# FC_Sheet2.net
KiCad netlist of a schematic drawn in Altium Designer
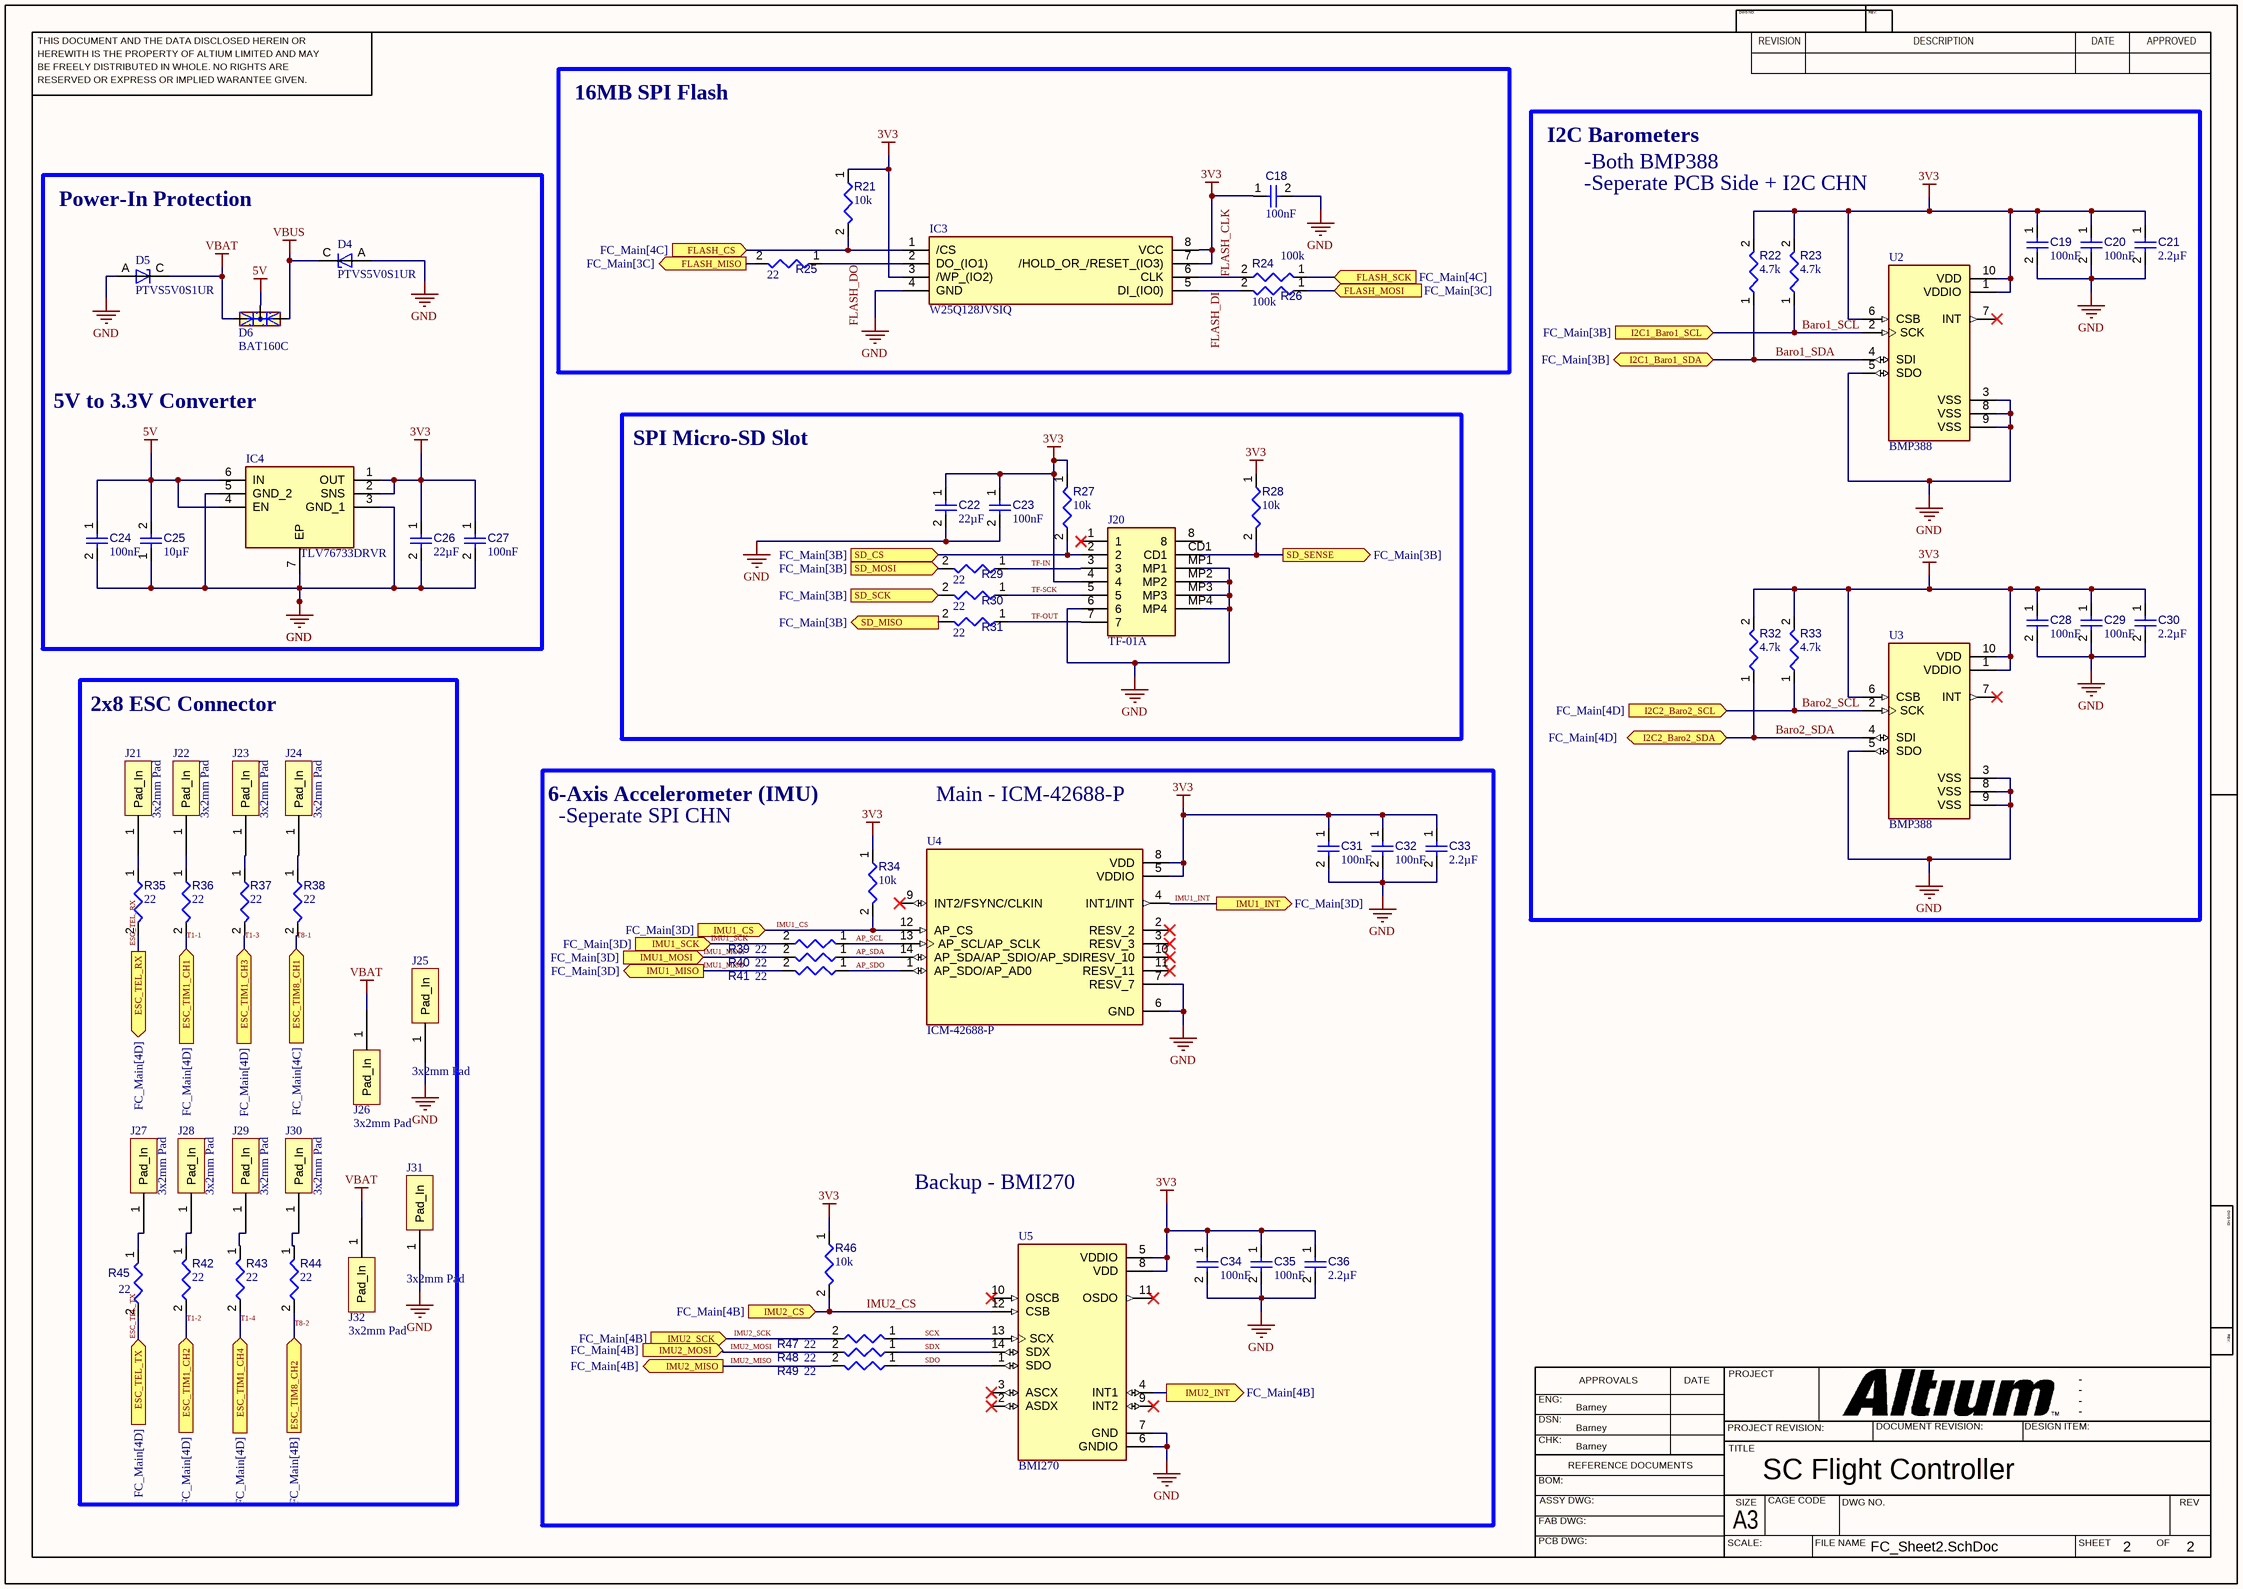
[diagram p0: FC_Sheet2.SchDoc]

(export (version "E")
  (design (tool "Eeschema 10.0.6"))
  (components
    (comp (ref "C18")
      (value "100nF")
      (footprint "CAPC0402(1005)60_L")
      (description "Chip Capacitor, 100nF +/-20%, 10V, 0402, Thickness 0.6 mm")
      (fields (field (name "TOLERANCE") "20%") (field (name "Comment") "Capacitor 100nF +/-20% 10V 0402"))
      (libsource (lib "Barney's Workspace") (part "CAP-NP-2"))
    )
    (comp (ref "C19")
      (value "100nF")
      (footprint "CAPC0402(1005)60_L")
      (description "Chip Capacitor, 100nF +/-20%, 10V, 0402, Thickness 0.6 mm")
      (fields (field (name "TOLERANCE") "20%") (field (name "Comment") "Capacitor 100nF +/-20% 10V 0402"))
      (libsource (lib "Barney's Workspace") (part "CAP-NP-2"))
    )
    (comp (ref "C20")
      (value "100nF")
      (footprint "CAPC0402(1005)60_L")
      (description "Chip Capacitor, 100nF +/-20%, 10V, 0402, Thickness 0.6 mm")
      (fields (field (name "TOLERANCE") "20%") (field (name "Comment") "Capacitor 100nF +/-20% 10V 0402"))
      (libsource (lib "Barney's Workspace") (part "CAP-NP-2"))
    )
    (comp (ref "C21")
      (value "2.2µF")
      (footprint "CAPC0402(1005)60_L")
      (description "Chip Capacitor, 2,2µF +/-20%, 10V, 0402, Thickness 0.6 mm")
      (fields (field (name "TOLERANCE") "10%") (field (name "Comment") "Capacitor 2,2µF +/-20% 10V 0402"))
      (libsource (lib "Barney's Workspace") (part "CAP-NP-2"))
    )
    (comp (ref "C22")
      (value "22µF")
      (footprint "CAPC0805(2012)145_L")
      (description "Chip Capacitor, 22µF +/-40%, 16V, 0805, Thickness 1.45 mm")
      (fields (field (name "TOLERANCE") "5%") (field (name "Comment") "Capacitor 22µF +/-40% 16V 0805"))
      (libsource (lib "Barney's Workspace") (part "CAP-NP-2"))
    )
    (comp (ref "C23")
      (value "100nF")
      (footprint "CAPC0402(1005)60_L")
      (description "Chip Capacitor, 100nF +/-20%, 10V, 0402, Thickness 0.6 mm")
      (fields (field (name "TOLERANCE") "20%") (field (name "Comment") "Capacitor 100nF +/-20% 10V 0402"))
      (libsource (lib "Barney's Workspace") (part "CAP-NP-2"))
    )
    (comp (ref "C24")
      (value "100nF")
      (footprint "CAPC0402(1005)60_L")
      (description "Chip Capacitor, 100nF +/-20%, 10V, 0402, Thickness 0.6 mm")
      (fields (field (name "TOLERANCE") "20%") (field (name "Comment") "Capacitor 100nF +/-20% 10V 0402"))
      (libsource (lib "Barney's Workspace") (part "CAP-NP-2"))
    )
    (comp (ref "C25")
      (value "10µF")
      (footprint "CAPC0603(1608)100_L")
      (description "Chip Capacitor, 10µF +/-20%, 10V, 0603, Thickness 1 mm")
      (fields (field (name "TOLERANCE") "10%") (field (name "Comment") "Capacitor 10µF +/-20% 10V 0603"))
      (libsource (lib "Barney's Workspace") (part "CAP-NP-2"))
    )
    (comp (ref "C26")
      (value "22µF")
      (footprint "CAPC0805(2012)145_L")
      (description "Chip Capacitor, 22µF +/-40%, 16V, 0805, Thickness 1.45 mm")
      (fields (field (name "TOLERANCE") "5%") (field (name "Comment") "Capacitor 22µF +/-40% 16V 0805"))
      (libsource (lib "Barney's Workspace") (part "CAP-NP-2"))
    )
    (comp (ref "C27")
      (value "100nF")
      (footprint "CAPC0402(1005)60_L")
      (description "Chip Capacitor, 100nF +/-20%, 10V, 0402, Thickness 0.6 mm")
      (fields (field (name "TOLERANCE") "20%") (field (name "Comment") "Capacitor 100nF +/-20% 10V 0402"))
      (libsource (lib "Barney's Workspace") (part "CAP-NP-2"))
    )
    (comp (ref "C28")
      (value "100nF")
      (footprint "CAPC0402(1005)60_L")
      (description "Chip Capacitor, 100nF +/-20%, 10V, 0402, Thickness 0.6 mm")
      (fields (field (name "TOLERANCE") "20%") (field (name "Comment") "Capacitor 100nF +/-20% 10V 0402"))
      (libsource (lib "Barney's Workspace") (part "CAP-NP-2"))
    )
    (comp (ref "C29")
      (value "100nF")
      (footprint "CAPC0402(1005)60_L")
      (description "Chip Capacitor, 100nF +/-20%, 10V, 0402, Thickness 0.6 mm")
      (fields (field (name "TOLERANCE") "20%") (field (name "Comment") "Capacitor 100nF +/-20% 10V 0402"))
      (libsource (lib "Barney's Workspace") (part "CAP-NP-2"))
    )
    (comp (ref "C30")
      (value "2.2µF")
      (footprint "CAPC0402(1005)60_L")
      (description "Chip Capacitor, 2,2µF +/-20%, 10V, 0402, Thickness 0.6 mm")
      (fields (field (name "TOLERANCE") "10%") (field (name "Comment") "Capacitor 2,2µF +/-20% 10V 0402"))
      (libsource (lib "Barney's Workspace") (part "CAP-NP-2"))
    )
    (comp (ref "C31")
      (value "100nF")
      (footprint "CAPC0402(1005)60_L")
      (description "Chip Capacitor, 100nF +/-20%, 10V, 0402, Thickness 0.6 mm")
      (fields (field (name "TOLERANCE") "20%") (field (name "Comment") "Capacitor 100nF +/-20% 10V 0402"))
      (libsource (lib "Barney's Workspace") (part "CAP-NP-2"))
    )
    (comp (ref "C32")
      (value "100nF")
      (footprint "CAPC0402(1005)60_L")
      (description "Chip Capacitor, 100nF +/-20%, 10V, 0402, Thickness 0.6 mm")
      (fields (field (name "TOLERANCE") "20%") (field (name "Comment") "Capacitor 100nF +/-20% 10V 0402"))
      (libsource (lib "Barney's Workspace") (part "CAP-NP-2"))
    )
    (comp (ref "C33")
      (value "2.2µF")
      (footprint "CAPC0402(1005)60_L")
      (description "Chip Capacitor, 2,2µF +/-20%, 10V, 0402, Thickness 0.6 mm")
      (fields (field (name "TOLERANCE") "10%") (field (name "Comment") "Capacitor 2,2µF +/-20% 10V 0402"))
      (libsource (lib "Barney's Workspace") (part "CAP-NP-2"))
    )
    (comp (ref "C34")
      (value "100nF")
      (footprint "CAPC0402(1005)60_L")
      (description "Chip Capacitor, 100nF +/-20%, 10V, 0402, Thickness 0.6 mm")
      (fields (field (name "TOLERANCE") "20%") (field (name "Comment") "Capacitor 100nF +/-20% 10V 0402"))
      (libsource (lib "Barney's Workspace") (part "CAP-NP-2"))
    )
    (comp (ref "C35")
      (value "100nF")
      (footprint "CAPC0402(1005)60_L")
      (description "Chip Capacitor, 100nF +/-20%, 10V, 0402, Thickness 0.6 mm")
      (fields (field (name "TOLERANCE") "20%") (field (name "Comment") "Capacitor 100nF +/-20% 10V 0402"))
      (libsource (lib "Barney's Workspace") (part "CAP-NP-2"))
    )
    (comp (ref "C36")
      (value "2.2µF")
      (footprint "CAPC0402(1005)60_L")
      (description "Chip Capacitor, 2,2µF +/-20%, 10V, 0402, Thickness 0.6 mm")
      (fields (field (name "TOLERANCE") "10%") (field (name "Comment") "Capacitor 2,2µF +/-20% 10V 0402"))
      (libsource (lib "Barney's Workspace") (part "CAP-NP-2"))
    )
    (comp (ref "D4")
      (value "PTVS5V0S1UR")
      (footprint "TVS_PTVS5V0S1UR")
      (description "9.2V Clamp 43.5A Ipp Tvs Diode Surface Mount SOD-123W")
      (fields (field (name "MF") "Nexperia USA"))
      (libsource (lib "Barney's Workspace") (part "PTVS5V0S1UR"))
    )
    (comp (ref "D5")
      (value "PTVS5V0S1UR")
      (footprint "TVS_PTVS5V0S1UR")
      (description "9.2V Clamp 43.5A Ipp Tvs Diode Surface Mount SOD-123W")
      (fields (field (name "MF") "Nexperia USA"))
      (libsource (lib "Barney's Workspace") (part "PTVS5V0S1UR"))
    )
    (comp (ref "D6")
      (value "BAT160C")
      (footprint "SOT223")
      (description "Diode Array 1 Pair Common Cathode Schottky 60 V 1A (DC) Surface Mount TO-261-4, TO-261AA")
      (fields (field (name "MF") "NXP Semiconductors"))
      (libsource (lib "Barney's Workspace") (part "BAT160C"))
    )
    (comp (ref "IC3")
      (value "W25Q128JVSIQ")
      (footprint "SamacSys:SOIC127P790X216-8N")
      (description "Integrated Circuit")
      (fields (field (name "MOUSER PART NUMBER") "454-W25Q128JVSIQ"))
      (libsource (lib "*") (part "W25Q128JVSIQ"))
    )
    (comp (ref "IC4")
      (value "TLV76733DRVR")
      (footprint "SamacSys:SON65P200X200X80-7N")
      (description "Integrated Circuit")
      (fields (field (name "MOUSER PART NUMBER") "595-TLV76733DRVR"))
      (libsource (lib "*") (part "TLV76733DRVR"))
    )
    (comp (ref "J20")
      (value "TF-01A")
      (footprint "SamacSys:TF01A")
      (description "Connector")
      (libsource (lib "*") (part "TF-01A"))
    )
    (comp (ref "J21")
      (value "3x2mm Pad")
      (footprint "3x2mm Pad-Footprint-1")
      (description "3mm x 2mm Pad to solder")
      (libsource (lib "") (part "3x2mm Pad-Symbol-1_1"))
    )
    (comp (ref "J22")
      (value "3x2mm Pad")
      (footprint "3x2mm Pad-Footprint-1")
      (description "3mm x 2mm Pad to solder")
      (libsource (lib "") (part "3x2mm Pad-Symbol-1_1"))
    )
    (comp (ref "J23")
      (value "3x2mm Pad")
      (footprint "3x2mm Pad-Footprint-1")
      (description "3mm x 2mm Pad to solder")
      (libsource (lib "") (part "3x2mm Pad-Symbol-1_1"))
    )
    (comp (ref "J24")
      (value "3x2mm Pad")
      (footprint "3x2mm Pad-Footprint-1")
      (description "3mm x 2mm Pad to solder")
      (libsource (lib "") (part "3x2mm Pad-Symbol-1_1"))
    )
    (comp (ref "J25")
      (value "3x2mm Pad")
      (footprint "3x2mm Pad-Footprint-1")
      (description "3mm x 2mm Pad to solder")
      (libsource (lib "") (part "3x2mm Pad-Symbol-1_1"))
    )
    (comp (ref "J26")
      (value "3x2mm Pad")
      (footprint "3x2mm Pad-Footprint-1")
      (description "3mm x 2mm Pad to solder")
      (libsource (lib "Barney's Workspace") (part "3x2mm Pad-Symbol-1"))
    )
    (comp (ref "J27")
      (value "3x2mm Pad")
      (footprint "3x2mm Pad-Footprint-1")
      (description "3mm x 2mm Pad to solder")
      (libsource (lib "") (part "3x2mm Pad-Symbol-1_1"))
    )
    (comp (ref "J28")
      (value "3x2mm Pad")
      (footprint "3x2mm Pad-Footprint-1")
      (description "3mm x 2mm Pad to solder")
      (libsource (lib "") (part "3x2mm Pad-Symbol-1_1"))
    )
    (comp (ref "J29")
      (value "3x2mm Pad")
      (footprint "3x2mm Pad-Footprint-1")
      (description "3mm x 2mm Pad to solder")
      (libsource (lib "") (part "3x2mm Pad-Symbol-1_1"))
    )
    (comp (ref "J30")
      (value "3x2mm Pad")
      (footprint "3x2mm Pad-Footprint-1")
      (description "3mm x 2mm Pad to solder")
      (libsource (lib "") (part "3x2mm Pad-Symbol-1_1"))
    )
    (comp (ref "J31")
      (value "3x2mm Pad")
      (footprint "3x2mm Pad-Footprint-1")
      (description "3mm x 2mm Pad to solder")
      (libsource (lib "") (part "3x2mm Pad-Symbol-1_1"))
    )
    (comp (ref "J32")
      (value "3x2mm Pad")
      (footprint "3x2mm Pad-Footprint-1")
      (description "3mm x 2mm Pad to solder")
      (libsource (lib "Barney's Workspace") (part "3x2mm Pad-Symbol-1"))
    )
    (comp (ref "R21")
      (value "10k")
      (footprint "RESC0402(1005)_L")
      (description "Chip Resistor, 10 kOhms, +/-1 %, 63 mW, -55 to 125 degC, 0402")
      (fields (field (name "POWER") "63mW") (field (name "TOLERANCE") "1%"))
      (libsource (lib "Barney's Workspace") (part "RES-2"))
    )
    (comp (ref "R22")
      (value "4.7k")
      (footprint "RESC0402(1005)_L")
      (description "4K7 0.063W 1% 0402 (1005 Metric)  SMD")
      (fields (field (name "TOLERANCE") "1%") (field (name "POWER") "63mW"))
      (libsource (lib "Barney's Workspace") (part "4D7KR2F"))
    )
    (comp (ref "R23")
      (value "4.7k")
      (footprint "RESC0402(1005)_L")
      (description "4K7 0.063W 1% 0402 (1005 Metric)  SMD")
      (fields (field (name "TOLERANCE") "1%") (field (name "POWER") "63mW"))
      (libsource (lib "Barney's Workspace") (part "4D7KR2F"))
    )
    (comp (ref "R24")
      (value "100k")
      (footprint "RESC0402(1005)_L")
      (description "Chip Resistor, 100 kOhms, +/-1 %, 63 mW, -55 to 155 degC, 0402")
      (fields (field (name "TOLERANCE") "1%") (field (name "POWER") "63mW"))
      (libsource (lib "Barney's Workspace") (part "RES-2"))
    )
    (comp (ref "R25")
      (value "22")
      (footprint "RESC0402(1005)_L")
      (description "Chip Resistor, 22Ohms, +/-1 %, 63 mW, -55 to 155 degC, 0402")
      (fields (field (name "TOLERANCE") "1%") (field (name "POWER") "63mW"))
      (libsource (lib "Barney's Workspace") (part "RES-2"))
    )
    (comp (ref "R26")
      (value "100k")
      (footprint "RESC0402(1005)_L")
      (description "Chip Resistor, 100 kOhms, +/-1 %, 63 mW, -55 to 155 degC, 0402")
      (fields (field (name "TOLERANCE") "1%") (field (name "POWER") "63mW"))
      (libsource (lib "Barney's Workspace") (part "RES-2"))
    )
    (comp (ref "R27")
      (value "10k")
      (footprint "RESC0402(1005)_L")
      (description "Chip Resistor, 10 kOhms, +/-1 %, 63 mW, -55 to 125 degC, 0402")
      (fields (field (name "POWER") "63mW") (field (name "TOLERANCE") "1%"))
      (libsource (lib "Barney's Workspace") (part "RES-2"))
    )
    (comp (ref "R28")
      (value "10k")
      (footprint "RESC0402(1005)_L")
      (description "Chip Resistor, 10 kOhms, +/-1 %, 63 mW, -55 to 125 degC, 0402")
      (fields (field (name "POWER") "63mW") (field (name "TOLERANCE") "1%"))
      (libsource (lib "Barney's Workspace") (part "RES-2"))
    )
    (comp (ref "R29")
      (value "22")
      (footprint "RESC0402(1005)_L")
      (description "Chip Resistor, 22Ohms, +/-1 %, 63 mW, -55 to 155 degC, 0402")
      (fields (field (name "TOLERANCE") "1%") (field (name "POWER") "63mW"))
      (libsource (lib "Barney's Workspace") (part "RES-2"))
    )
    (comp (ref "R30")
      (value "22")
      (footprint "RESC0402(1005)_L")
      (description "Chip Resistor, 22Ohms, +/-1 %, 63 mW, -55 to 155 degC, 0402")
      (fields (field (name "TOLERANCE") "1%") (field (name "POWER") "63mW"))
      (libsource (lib "Barney's Workspace") (part "RES-2"))
    )
    (comp (ref "R31")
      (value "22")
      (footprint "RESC0402(1005)_L")
      (description "Chip Resistor, 22Ohms, +/-1 %, 63 mW, -55 to 155 degC, 0402")
      (fields (field (name "TOLERANCE") "1%") (field (name "POWER") "63mW"))
      (libsource (lib "Barney's Workspace") (part "RES-2"))
    )
    (comp (ref "R32")
      (value "4.7k")
      (footprint "RESC0402(1005)_L")
      (description "4K7 0.063W 1% 0402 (1005 Metric)  SMD")
      (fields (field (name "TOLERANCE") "1%") (field (name "POWER") "63mW"))
      (libsource (lib "Barney's Workspace") (part "4D7KR2F"))
    )
    (comp (ref "R33")
      (value "4.7k")
      (footprint "RESC0402(1005)_L")
      (description "4K7 0.063W 1% 0402 (1005 Metric)  SMD")
      (fields (field (name "TOLERANCE") "1%") (field (name "POWER") "63mW"))
      (libsource (lib "Barney's Workspace") (part "4D7KR2F"))
    )
    (comp (ref "R34")
      (value "10k")
      (footprint "RESC0402(1005)_L")
      (description "Chip Resistor, 10 kOhms, +/-1 %, 63 mW, -55 to 125 degC, 0402")
      (fields (field (name "POWER") "63mW") (field (name "TOLERANCE") "1%"))
      (libsource (lib "Barney's Workspace") (part "RES-2"))
    )
    (comp (ref "R35")
      (value "22")
      (footprint "RESC0402(1005)_L")
      (description "Chip Resistor, 22Ohms, +/-1 %, 63 mW, -55 to 155 degC, 0402")
      (fields (field (name "TOLERANCE") "1%") (field (name "POWER") "63mW"))
      (libsource (lib "Barney's Workspace") (part "RES-2"))
    )
    (comp (ref "R36")
      (value "22")
      (footprint "RESC0402(1005)_L")
      (description "Chip Resistor, 22Ohms, +/-1 %, 63 mW, -55 to 155 degC, 0402")
      (fields (field (name "TOLERANCE") "1%") (field (name "POWER") "63mW"))
      (libsource (lib "Barney's Workspace") (part "RES-2"))
    )
    (comp (ref "R37")
      (value "22")
      (footprint "RESC0402(1005)_L")
      (description "Chip Resistor, 22Ohms, +/-1 %, 63 mW, -55 to 155 degC, 0402")
      (fields (field (name "TOLERANCE") "1%") (field (name "POWER") "63mW"))
      (libsource (lib "Barney's Workspace") (part "RES-2"))
    )
    (comp (ref "R38")
      (value "22")
      (footprint "RESC0402(1005)_L")
      (description "Chip Resistor, 22Ohms, +/-1 %, 63 mW, -55 to 155 degC, 0402")
      (fields (field (name "TOLERANCE") "1%") (field (name "POWER") "63mW"))
      (libsource (lib "Barney's Workspace") (part "RES-2"))
    )
    (comp (ref "R39")
      (value "22")
      (footprint "RESC0402(1005)_L")
      (description "Chip Resistor, 22Ohms, +/-1 %, 63 mW, -55 to 155 degC, 0402")
      (fields (field (name "TOLERANCE") "1%") (field (name "POWER") "63mW"))
      (libsource (lib "Barney's Workspace") (part "RES-2"))
    )
    (comp (ref "R40")
      (value "22")
      (footprint "RESC0402(1005)_L")
      (description "Chip Resistor, 22Ohms, +/-1 %, 63 mW, -55 to 155 degC, 0402")
      (fields (field (name "TOLERANCE") "1%") (field (name "POWER") "63mW"))
      (libsource (lib "Barney's Workspace") (part "RES-2"))
    )
    (comp (ref "R41")
      (value "22")
      (footprint "RESC0402(1005)_L")
      (description "Chip Resistor, 22Ohms, +/-1 %, 63 mW, -55 to 155 degC, 0402")
      (fields (field (name "TOLERANCE") "1%") (field (name "POWER") "63mW"))
      (libsource (lib "Barney's Workspace") (part "RES-2"))
    )
    (comp (ref "R42")
      (value "22")
      (footprint "RESC0402(1005)_L")
      (description "Chip Resistor, 22Ohms, +/-1 %, 63 mW, -55 to 155 degC, 0402")
      (fields (field (name "TOLERANCE") "1%") (field (name "POWER") "63mW"))
      (libsource (lib "Barney's Workspace") (part "RES-2"))
    )
    (comp (ref "R43")
      (value "22")
      (footprint "RESC0402(1005)_L")
      (description "Chip Resistor, 22Ohms, +/-1 %, 63 mW, -55 to 155 degC, 0402")
      (fields (field (name "TOLERANCE") "1%") (field (name "POWER") "63mW"))
      (libsource (lib "Barney's Workspace") (part "RES-2"))
    )
    (comp (ref "R44")
      (value "22")
      (footprint "RESC0402(1005)_L")
      (description "Chip Resistor, 22Ohms, +/-1 %, 63 mW, -55 to 155 degC, 0402")
      (fields (field (name "TOLERANCE") "1%") (field (name "POWER") "63mW"))
      (libsource (lib "Barney's Workspace") (part "RES-2"))
    )
    (comp (ref "R45")
      (value "22")
      (footprint "RESC0402(1005)_L")
      (description "Chip Resistor, 22Ohms, +/-1 %, 63 mW, -55 to 155 degC, 0402")
      (fields (field (name "TOLERANCE") "1%") (field (name "POWER") "63mW"))
      (libsource (lib "Barney's Workspace") (part "RES-2"))
    )
    (comp (ref "R46")
      (value "10k")
      (footprint "RESC0402(1005)_L")
      (description "Chip Resistor, 10 kOhms, +/-1 %, 63 mW, -55 to 125 degC, 0402")
      (fields (field (name "POWER") "63mW") (field (name "TOLERANCE") "1%"))
      (libsource (lib "Barney's Workspace") (part "RES-2"))
    )
    (comp (ref "R47")
      (value "22")
      (footprint "RESC0402(1005)_L")
      (description "Chip Resistor, 22Ohms, +/-1 %, 63 mW, -55 to 155 degC, 0402")
      (fields (field (name "TOLERANCE") "1%") (field (name "POWER") "63mW"))
      (libsource (lib "Barney's Workspace") (part "RES-2"))
    )
    (comp (ref "R48")
      (value "22")
      (footprint "RESC0402(1005)_L")
      (description "Chip Resistor, 22Ohms, +/-1 %, 63 mW, -55 to 155 degC, 0402")
      (fields (field (name "TOLERANCE") "1%") (field (name "POWER") "63mW"))
      (libsource (lib "Barney's Workspace") (part "RES-2"))
    )
    (comp (ref "R49")
      (value "22")
      (footprint "RESC0402(1005)_L")
      (description "Chip Resistor, 22Ohms, +/-1 %, 63 mW, -55 to 155 degC, 0402")
      (fields (field (name "TOLERANCE") "1%") (field (name "POWER") "63mW"))
      (libsource (lib "Barney's Workspace") (part "RES-2"))
    )
    (comp (ref "U2")
      (value "BMP388")
      (footprint "PQFN50P200X200X80-10N")
      (description "P-Sensor SPI I2C 1, 25 Bar SMD")
      (libsource (lib "Barney's Workspace") (part "BMP388"))
    )
    (comp (ref "U3")
      (value "BMP388")
      (footprint "PQFN50P200X200X80-10N")
      (description "P-Sensor SPI I2C 1, 25 Bar SMD")
      (libsource (lib "Barney's Workspace") (part "BMP388"))
    )
    (comp (ref "U4")
      (value "ICM-42688-P")
      (footprint "PQFN50P300X250X97-14N")
      (description "Accelerometer, Gyroscope, 6 Axis Sensor Output")
      (libsource (lib "Barney's Workspace") (part "ICM-42688-P"))
    )
    (comp (ref "U5")
      (value "BMI270")
      (footprint "XDCR_BMI270")
      (description "Accelerometer, Gyroscope, 6 Axis Sensor IÂ²C, SPI Output")
      (fields (field (name "DIGI-KEY_PART_NUMBER") "828-1091-2-ND") (field (name "MF") "Bosch Sensortec"))
      (libsource (lib "Barney's Workspace") (part "BMI270"))
    )
  )
  (nets
    (net (code "1") (name "/AP_SCL") (class "Default")
      (node (ref "R39") (pin "1") (pinfunction "1_1") (pintype "passive"))
      (node (ref "U4") (pin "13") (pinfunction "AP_SCL/AP_SCLK_13") (pintype "input"))
    )
    (net (code "2") (name "/AP_SDA") (class "Default")
      (node (ref "R40") (pin "1") (pinfunction "1_1") (pintype "passive"))
      (node (ref "U4") (pin "14") (pinfunction "AP_SDA/AP_SDIO/AP_SDI_14") (pintype "bidirectional"))
    )
    (net (code "3") (name "/AP_SDO") (class "Default")
      (node (ref "R41") (pin "1") (pinfunction "1_1") (pintype "passive"))
      (node (ref "U4") (pin "1") (pinfunction "AP_SDO/AP_AD0_1") (pintype "bidirectional"))
    )
    (net (code "4") (name "/Baro1_SCL") (class "Default")
      (node (ref "R23") (pin "1") (pinfunction "1_1") (pintype "passive"))
      (node (ref "U2") (pin "2") (pinfunction "SCK_2") (pintype "input"))
    )
    (net (code "5") (name "/Baro1_SDA") (class "Default")
      (node (ref "R22") (pin "1") (pinfunction "1_1") (pintype "passive"))
      (node (ref "U2") (pin "4") (pinfunction "SDI_4") (pintype "bidirectional"))
    )
    (net (code "6") (name "/Baro2_SCL") (class "Default")
      (node (ref "R33") (pin "1") (pinfunction "1_1") (pintype "passive"))
      (node (ref "U3") (pin "2") (pinfunction "SCK_2") (pintype "input"))
    )
    (net (code "7") (name "/Baro2_SDA") (class "Default")
      (node (ref "R32") (pin "1") (pinfunction "1_1") (pintype "passive"))
      (node (ref "U3") (pin "4") (pinfunction "SDI_4") (pintype "bidirectional"))
    )
    (net (code "8") (name "/ESC_TEL_RX") (class "Default")
      (node (ref "R35") (pin "2") (pinfunction "2_2") (pintype "passive"))
    )
    (net (code "9") (name "/ESC_TEL_TX") (class "Default")
      (node (ref "R45") (pin "2") (pinfunction "2_2") (pintype "passive"))
    )
    (net (code "10") (name "/FLASH_CLK") (class "Default")
      (node (ref "IC3") (pin "6") (pinfunction "CLK_6") (pintype "passive"))
      (node (ref "R24") (pin "2") (pinfunction "2_2") (pintype "passive"))
    )
    (net (code "11") (name "/FLASH_CS") (class "Default")
      (node (ref "IC3") (pin "1") (pinfunction "/CS_1") (pintype "passive"))
      (node (ref "R21") (pin "2") (pinfunction "2_2") (pintype "passive"))
    )
    (net (code "12") (name "/FLASH_DI") (class "Default")
      (node (ref "IC3") (pin "5") (pinfunction "DI_(IO0)_5") (pintype "passive"))
      (node (ref "R26") (pin "2") (pinfunction "2_2") (pintype "passive"))
    )
    (net (code "13") (name "/FLASH_DO") (class "Default")
      (node (ref "IC3") (pin "2") (pinfunction "DO_(IO1)_2") (pintype "passive"))
      (node (ref "R25") (pin "1") (pinfunction "1_1") (pintype "passive"))
    )
    (net (code "14") (name "/FLASH_MISO") (class "Default")
      (node (ref "R25") (pin "2") (pinfunction "2_2") (pintype "passive"))
    )
    (net (code "15") (name "/FLASH_MOSI") (class "Default")
      (node (ref "R26") (pin "1") (pinfunction "1_1") (pintype "passive"))
    )
    (net (code "16") (name "/FLASH_SCK") (class "Default")
      (node (ref "R24") (pin "1") (pinfunction "1_1") (pintype "passive"))
    )
    (net (code "17") (name "/IMU1_CS") (class "Default")
      (node (ref "R34") (pin "2") (pinfunction "2_2") (pintype "passive"))
      (node (ref "U4") (pin "12") (pinfunction "AP_CS_12") (pintype "input"))
    )
    (net (code "18") (name "/IMU1_INT") (class "Default")
      (node (ref "U4") (pin "4") (pinfunction "INT1/INT_4") (pintype "output"))
    )
    (net (code "19") (name "/IMU1_MISO") (class "Default")
      (node (ref "R41") (pin "2") (pinfunction "2_2") (pintype "passive"))
    )
    (net (code "20") (name "/IMU1_MOSI") (class "Default")
      (node (ref "R40") (pin "2") (pinfunction "2_2") (pintype "passive"))
    )
    (net (code "21") (name "/IMU1_SCK") (class "Default")
      (node (ref "R39") (pin "2") (pinfunction "2_2") (pintype "passive"))
    )
    (net (code "22") (name "/IMU2_CS") (class "Default")
      (node (ref "R46") (pin "2") (pinfunction "2_2") (pintype "passive"))
      (node (ref "U5") (pin "12") (pinfunction "CSB_12") (pintype "input"))
    )
    (net (code "23") (name "/IMU2_INT") (class "Default")
      (node (ref "U5") (pin "4") (pinfunction "INT1_4") (pintype "bidirectional"))
    )
    (net (code "24") (name "/IMU2_MISO") (class "Default")
      (node (ref "R49") (pin "2") (pinfunction "2_2") (pintype "passive"))
    )
    (net (code "25") (name "/IMU2_MOSI") (class "Default")
      (node (ref "R48") (pin "2") (pinfunction "2_2") (pintype "passive"))
    )
    (net (code "26") (name "/IMU2_SCK") (class "Default")
      (node (ref "R47") (pin "2") (pinfunction "2_2") (pintype "passive"))
    )
    (net (code "27") (name "/SCX") (class "Default")
      (node (ref "R47") (pin "1") (pinfunction "1_1") (pintype "passive"))
      (node (ref "U5") (pin "13") (pinfunction "SCX_13") (pintype "input"))
    )
    (net (code "28") (name "/SDO") (class "Default")
      (node (ref "R49") (pin "1") (pinfunction "1_1") (pintype "passive"))
      (node (ref "U5") (pin "1") (pinfunction "SDO_1") (pintype "bidirectional"))
    )
    (net (code "29") (name "/SDX") (class "Default")
      (node (ref "R48") (pin "1") (pinfunction "1_1") (pintype "passive"))
      (node (ref "U5") (pin "14") (pinfunction "SDX_14") (pintype "bidirectional"))
    )
    (net (code "30") (name "/SD_CS") (class "Default")
      (node (ref "J20") (pin "2") (pinfunction "2_2") (pintype "passive"))
      (node (ref "R27") (pin "2") (pinfunction "2_2") (pintype "passive"))
    )
    (net (code "31") (name "/SD_MISO") (class "Default")
      (node (ref "R31") (pin "2") (pinfunction "2_2") (pintype "passive"))
    )
    (net (code "32") (name "/SD_MOSI") (class "Default")
      (node (ref "R29") (pin "2") (pinfunction "2_2") (pintype "passive"))
    )
    (net (code "33") (name "/SD_SCK") (class "Default")
      (node (ref "R30") (pin "2") (pinfunction "2_2") (pintype "passive"))
    )
    (net (code "34") (name "/SD_SENSE") (class "Default")
      (node (ref "J20") (pin "CD1") (pinfunction "CD1_CD1") (pintype "passive"))
      (node (ref "R28") (pin "2") (pinfunction "2_2") (pintype "passive"))
    )
    (net (code "35") (name "/T1-1") (class "Default")
      (node (ref "R36") (pin "2") (pinfunction "2_2") (pintype "passive"))
    )
    (net (code "36") (name "/T1-2") (class "Default")
      (node (ref "R42") (pin "2") (pinfunction "2_2") (pintype "passive"))
    )
    (net (code "37") (name "/T1-3") (class "Default")
      (node (ref "R37") (pin "2") (pinfunction "2_2") (pintype "passive"))
    )
    (net (code "38") (name "/T1-4") (class "Default")
      (node (ref "R43") (pin "2") (pinfunction "2_2") (pintype "passive"))
    )
    (net (code "39") (name "/T8-1") (class "Default")
      (node (ref "R38") (pin "2") (pinfunction "2_2") (pintype "passive"))
    )
    (net (code "40") (name "/T8-2") (class "Default")
      (node (ref "R44") (pin "2") (pinfunction "2_2") (pintype "passive"))
    )
    (net (code "41") (name "/TF-IN") (class "Default")
      (node (ref "J20") (pin "3") (pinfunction "3_3") (pintype "passive"))
      (node (ref "R29") (pin "1") (pinfunction "1_1") (pintype "passive"))
    )
    (net (code "42") (name "/TF-OUT") (class "Default")
      (node (ref "J20") (pin "7") (pinfunction "7_7") (pintype "passive"))
      (node (ref "R31") (pin "1") (pinfunction "1_1") (pintype "passive"))
    )
    (net (code "43") (name "/TF-SCK") (class "Default")
      (node (ref "J20") (pin "5") (pinfunction "5_5") (pintype "passive"))
      (node (ref "R30") (pin "1") (pinfunction "1_1") (pintype "passive"))
    )
    (net (code "44") (name "3V3") (class "Default")
      (node (ref "C18") (pin "1") (pinfunction "1_1") (pintype "passive"))
      (node (ref "C19") (pin "1") (pinfunction "1_1") (pintype "passive"))
      (node (ref "C20") (pin "1") (pinfunction "1_1") (pintype "passive"))
      (node (ref "C21") (pin "1") (pinfunction "1_1") (pintype "passive"))
      (node (ref "C22") (pin "1") (pinfunction "1_1") (pintype "passive"))
      (node (ref "C23") (pin "1") (pinfunction "1_1") (pintype "passive"))
      (node (ref "C26") (pin "1") (pinfunction "1_1") (pintype "passive"))
      (node (ref "C27") (pin "1") (pinfunction "1_1") (pintype "passive"))
      (node (ref "C28") (pin "1") (pinfunction "1_1") (pintype "passive"))
      (node (ref "C29") (pin "1") (pinfunction "1_1") (pintype "passive"))
      (node (ref "C30") (pin "1") (pinfunction "1_1") (pintype "passive"))
      (node (ref "C31") (pin "1") (pinfunction "1_1") (pintype "passive"))
      (node (ref "C32") (pin "1") (pinfunction "1_1") (pintype "passive"))
      (node (ref "C33") (pin "1") (pinfunction "1_1") (pintype "passive"))
      (node (ref "C34") (pin "1") (pinfunction "1_1") (pintype "passive"))
      (node (ref "C35") (pin "1") (pinfunction "1_1") (pintype "passive"))
      (node (ref "C36") (pin "1") (pinfunction "1_1") (pintype "passive"))
      (node (ref "IC3") (pin "3") (pinfunction "/WP_(IO2)_3") (pintype "passive"))
      (node (ref "IC3") (pin "7") (pinfunction "/HOLD_OR_/RESET_(IO3)_7") (pintype "passive"))
      (node (ref "IC3") (pin "8") (pinfunction "VCC_8") (pintype "passive"))
      (node (ref "IC4") (pin "1") (pinfunction "OUT_1") (pintype "passive"))
      (node (ref "IC4") (pin "2") (pinfunction "SNS_2") (pintype "passive"))
      (node (ref "J20") (pin "4") (pinfunction "4_4") (pintype "passive"))
      (node (ref "R21") (pin "1") (pinfunction "1_1") (pintype "passive"))
      (node (ref "R22") (pin "2") (pinfunction "2_2") (pintype "passive"))
      (node (ref "R23") (pin "2") (pinfunction "2_2") (pintype "passive"))
      (node (ref "R27") (pin "1") (pinfunction "1_1") (pintype "passive"))
      (node (ref "R28") (pin "1") (pinfunction "1_1") (pintype "passive"))
      (node (ref "R32") (pin "2") (pinfunction "2_2") (pintype "passive"))
      (node (ref "R33") (pin "2") (pinfunction "2_2") (pintype "passive"))
      (node (ref "R34") (pin "1") (pinfunction "1_1") (pintype "passive"))
      (node (ref "R46") (pin "1") (pinfunction "1_1") (pintype "passive"))
      (node (ref "U2") (pin "1") (pinfunction "VDDIO_1") (pintype "power_in"))
      (node (ref "U2") (pin "10") (pinfunction "VDD_10") (pintype "power_in"))
      (node (ref "U2") (pin "6") (pinfunction "CSB_6") (pintype "input"))
      (node (ref "U3") (pin "1") (pinfunction "VDDIO_1") (pintype "power_in"))
      (node (ref "U3") (pin "10") (pinfunction "VDD_10") (pintype "power_in"))
      (node (ref "U3") (pin "6") (pinfunction "CSB_6") (pintype "input"))
      (node (ref "U4") (pin "5") (pinfunction "VDDIO_5") (pintype "power_in"))
      (node (ref "U4") (pin "8") (pinfunction "VDD_8") (pintype "power_in"))
      (node (ref "U5") (pin "5") (pinfunction "VDDIO_5") (pintype "power_in"))
      (node (ref "U5") (pin "8") (pinfunction "VDD_8") (pintype "power_in"))
    )
    (net (code "45") (name "5V") (class "Default")
      (node (ref "C24") (pin "1") (pinfunction "1_1") (pintype "passive"))
      (node (ref "C25") (pin "2") (pinfunction "2_2") (pintype "passive"))
      (node (ref "D6") (pin "4") (pinfunction "K1K2_4") (pintype "passive"))
      (node (ref "IC4") (pin "4") (pinfunction "EN_4") (pintype "passive"))
      (node (ref "IC4") (pin "6") (pinfunction "IN_6") (pintype "passive"))
    )
    (net (code "46") (name "GND") (class "Default")
      (node (ref "C18") (pin "2") (pinfunction "2_2") (pintype "passive"))
      (node (ref "C19") (pin "2") (pinfunction "2_2") (pintype "passive"))
      (node (ref "C20") (pin "2") (pinfunction "2_2") (pintype "passive"))
      (node (ref "C21") (pin "2") (pinfunction "2_2") (pintype "passive"))
      (node (ref "C22") (pin "2") (pinfunction "2_2") (pintype "passive"))
      (node (ref "C23") (pin "2") (pinfunction "2_2") (pintype "passive"))
      (node (ref "C24") (pin "2") (pinfunction "2_2") (pintype "passive"))
      (node (ref "C25") (pin "1") (pinfunction "1_1") (pintype "passive"))
      (node (ref "C26") (pin "2") (pinfunction "2_2") (pintype "passive"))
      (node (ref "C27") (pin "2") (pinfunction "2_2") (pintype "passive"))
      (node (ref "C28") (pin "2") (pinfunction "2_2") (pintype "passive"))
      (node (ref "C29") (pin "2") (pinfunction "2_2") (pintype "passive"))
      (node (ref "C30") (pin "2") (pinfunction "2_2") (pintype "passive"))
      (node (ref "C31") (pin "2") (pinfunction "2_2") (pintype "passive"))
      (node (ref "C32") (pin "2") (pinfunction "2_2") (pintype "passive"))
      (node (ref "C33") (pin "2") (pinfunction "2_2") (pintype "passive"))
      (node (ref "C34") (pin "2") (pinfunction "2_2") (pintype "passive"))
      (node (ref "C35") (pin "2") (pinfunction "2_2") (pintype "passive"))
      (node (ref "C36") (pin "2") (pinfunction "2_2") (pintype "passive"))
      (node (ref "D4") (pin "A") (pinfunction "A_A") (pintype "passive"))
      (node (ref "D5") (pin "A") (pinfunction "A_A") (pintype "passive"))
      (node (ref "IC3") (pin "4") (pinfunction "GND_4") (pintype "passive"))
      (node (ref "IC4") (pin "3") (pinfunction "GND_1_3") (pintype "passive"))
      (node (ref "IC4") (pin "5") (pinfunction "GND_2_5") (pintype "passive"))
      (node (ref "IC4") (pin "7") (pinfunction "EP_7") (pintype "passive"))
      (node (ref "J20") (pin "6") (pinfunction "6_6") (pintype "passive"))
      (node (ref "J20") (pin "MP1") (pinfunction "MP1_MP1") (pintype "passive"))
      (node (ref "J20") (pin "MP2") (pinfunction "MP2_MP2") (pintype "passive"))
      (node (ref "J20") (pin "MP3") (pinfunction "MP3_MP3") (pintype "passive"))
      (node (ref "J20") (pin "MP4") (pinfunction "MP4_MP4") (pintype "passive"))
      (node (ref "J25") (pin "1") (pinfunction "Pad_In_1") (pintype "passive"))
      (node (ref "J31") (pin "1") (pinfunction "Pad_In_1") (pintype "passive"))
      (node (ref "U2") (pin "3") (pinfunction "VSS_3") (pintype "power_in"))
      (node (ref "U2") (pin "5") (pinfunction "SDO_5") (pintype "bidirectional"))
      (node (ref "U2") (pin "8") (pinfunction "VSS_8") (pintype "power_in"))
      (node (ref "U2") (pin "9") (pinfunction "VSS_9") (pintype "power_in"))
      (node (ref "U3") (pin "3") (pinfunction "VSS_3") (pintype "power_in"))
      (node (ref "U3") (pin "5") (pinfunction "SDO_5") (pintype "bidirectional"))
      (node (ref "U3") (pin "8") (pinfunction "VSS_8") (pintype "power_in"))
      (node (ref "U3") (pin "9") (pinfunction "VSS_9") (pintype "power_in"))
      (node (ref "U4") (pin "6") (pinfunction "GND_6") (pintype "power_in"))
      (node (ref "U4") (pin "7") (pinfunction "RESV_7_7") (pintype "passive"))
      (node (ref "U5") (pin "6") (pinfunction "GNDIO_6") (pintype "power_in"))
      (node (ref "U5") (pin "7") (pinfunction "GND_7") (pintype "power_in"))
    )
    (net (code "47") (name "Net-(J21-Pad_In)") (class "Default")
      (node (ref "J21") (pin "1") (pinfunction "Pad_In_1") (pintype "passive"))
      (node (ref "R35") (pin "1") (pinfunction "1_1") (pintype "passive"))
    )
    (net (code "48") (name "Net-(J22-Pad_In)") (class "Default")
      (node (ref "J22") (pin "1") (pinfunction "Pad_In_1") (pintype "passive"))
      (node (ref "R36") (pin "1") (pinfunction "1_1") (pintype "passive"))
    )
    (net (code "49") (name "Net-(J23-Pad_In)") (class "Default")
      (node (ref "J23") (pin "1") (pinfunction "Pad_In_1") (pintype "passive"))
      (node (ref "R37") (pin "1") (pinfunction "1_1") (pintype "passive"))
    )
    (net (code "50") (name "Net-(J24-Pad_In)") (class "Default")
      (node (ref "J24") (pin "1") (pinfunction "Pad_In_1") (pintype "passive"))
      (node (ref "R38") (pin "1") (pinfunction "1_1") (pintype "passive"))
    )
    (net (code "51") (name "Net-(J27-Pad_In)") (class "Default")
      (node (ref "J27") (pin "1") (pinfunction "Pad_In_1") (pintype "passive"))
      (node (ref "R45") (pin "1") (pinfunction "1_1") (pintype "passive"))
    )
    (net (code "52") (name "Net-(J28-Pad_In)") (class "Default")
      (node (ref "J28") (pin "1") (pinfunction "Pad_In_1") (pintype "passive"))
      (node (ref "R42") (pin "1") (pinfunction "1_1") (pintype "passive"))
    )
    (net (code "53") (name "Net-(J29-Pad_In)") (class "Default")
      (node (ref "J29") (pin "1") (pinfunction "Pad_In_1") (pintype "passive"))
      (node (ref "R43") (pin "1") (pinfunction "1_1") (pintype "passive"))
    )
    (net (code "54") (name "Net-(J30-Pad_In)") (class "Default")
      (node (ref "J30") (pin "1") (pinfunction "Pad_In_1") (pintype "passive"))
      (node (ref "R44") (pin "1") (pinfunction "1_1") (pintype "passive"))
    )
    (net (code "55") (name "VBAT") (class "Default")
      (node (ref "D5") (pin "C") (pinfunction "C_C") (pintype "passive"))
      (node (ref "D6") (pin "1") (pinfunction "A1_1") (pintype "passive"))
      (node (ref "J26") (pin "1") (pinfunction "Pad_In_1") (pintype "passive"))
      (node (ref "J32") (pin "1") (pinfunction "Pad_In_1") (pintype "passive"))
    )
    (net (code "56") (name "VBUS") (class "Default")
      (node (ref "D4") (pin "C") (pinfunction "C_C") (pintype "passive"))
      (node (ref "D6") (pin "3") (pinfunction "A2_3") (pintype "passive"))
    )
    (net (code "57") (name "unconnected-(J20-Pad1)") (class "Default")
      (node (ref "J20") (pin "1") (pinfunction "1_1") (pintype "passive+no_connect"))
    )
    (net (code "58") (name "unconnected-(J20-Pad8)") (class "Default")
      (node (ref "J20") (pin "8") (pinfunction "8_8") (pintype "passive"))
    )
    (net (code "59") (name "unconnected-(U2-INT-Pad7)") (class "Default")
      (node (ref "U2") (pin "7") (pinfunction "INT_7") (pintype "output+no_connect"))
    )
    (net (code "60") (name "unconnected-(U3-INT-Pad7)") (class "Default")
      (node (ref "U3") (pin "7") (pinfunction "INT_7") (pintype "output+no_connect"))
    )
    (net (code "61") (name "unconnected-(U4-INT2{slash}FSYNC{slash}CLKIN-Pad9)") (class "Default")
      (node (ref "U4") (pin "9") (pinfunction "INT2/FSYNC/CLKIN_9") (pintype "bidirectional+no_connect"))
    )
    (net (code "62") (name "unconnected-(U4-RESV_2-Pad2)") (class "Default")
      (node (ref "U4") (pin "2") (pinfunction "RESV_2_2") (pintype "passive+no_connect"))
    )
    (net (code "63") (name "unconnected-(U4-RESV_3-Pad3)") (class "Default")
      (node (ref "U4") (pin "3") (pinfunction "RESV_3_3") (pintype "passive+no_connect"))
    )
    (net (code "64") (name "unconnected-(U4-RESV_10-Pad10)") (class "Default")
      (node (ref "U4") (pin "10") (pinfunction "RESV_10_10") (pintype "passive+no_connect"))
    )
    (net (code "65") (name "unconnected-(U4-RESV_11-Pad11)") (class "Default")
      (node (ref "U4") (pin "11") (pinfunction "RESV_11_11") (pintype "passive+no_connect"))
    )
    (net (code "66") (name "unconnected-(U5-ASCX-Pad3)") (class "Default")
      (node (ref "U5") (pin "3") (pinfunction "ASCX_3") (pintype "bidirectional+no_connect"))
    )
    (net (code "67") (name "unconnected-(U5-ASDX-Pad2)") (class "Default")
      (node (ref "U5") (pin "2") (pinfunction "ASDX_2") (pintype "bidirectional+no_connect"))
    )
    (net (code "68") (name "unconnected-(U5-INT2-Pad9)") (class "Default")
      (node (ref "U5") (pin "9") (pinfunction "INT2_9") (pintype "bidirectional+no_connect"))
    )
    (net (code "69") (name "unconnected-(U5-OSCB-Pad10)") (class "Default")
      (node (ref "U5") (pin "10") (pinfunction "OSCB_10") (pintype "input+no_connect"))
    )
    (net (code "70") (name "unconnected-(U5-OSDO-Pad11)") (class "Default")
      (node (ref "U5") (pin "11") (pinfunction "OSDO_11") (pintype "output+no_connect"))
    )
  )
)
